# Main.net
KiCad netlist of a schematic drawn in Altium Designer
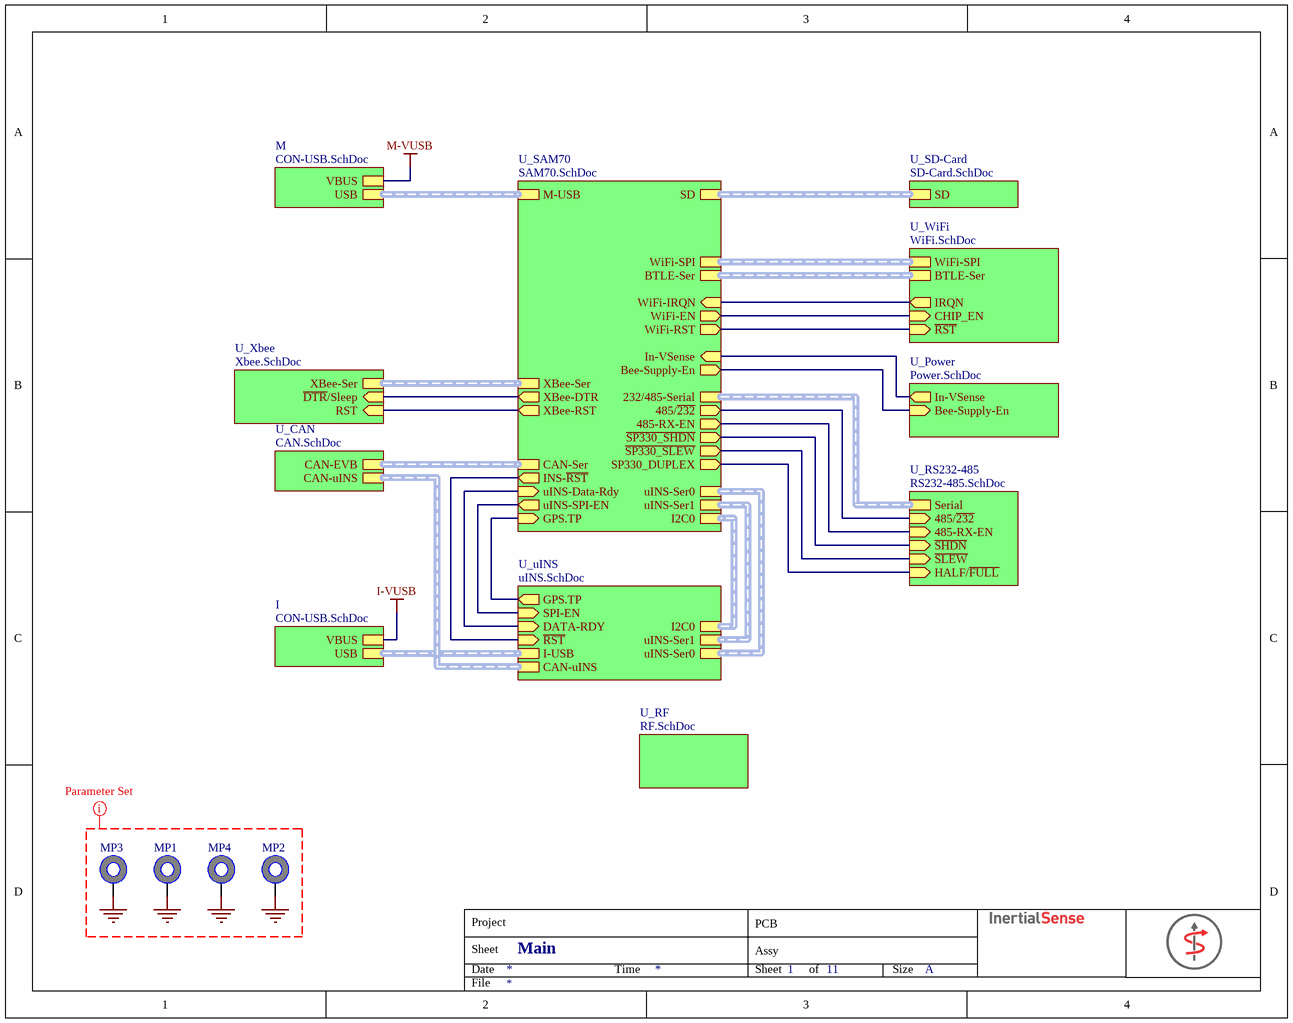
[diagram p0: Main.SchDoc]

(export (version "E")
  (design (tool "Eeschema 10.0.6"))
  (components
    (comp (ref "MP1")
      (value "Standoff")
      (footprint "9774050151R")
      (description "RND STANDOFF M2.5X0.45 STEEL 5MM")
      (fields
        (field (name "MANUFACTURER") "Wurth Electronics")
        (field (name "MANUFACTURER PART NUMBER") "9774050951R")
      )
      (libsource (lib "General") (part "Standoff"))
    )
    (comp (ref "MP2")
      (value "Standoff")
      (footprint "9774050151R")
      (description "RND STANDOFF M2.5X0.45 STEEL 5MM")
      (fields
        (field (name "MANUFACTURER") "Wurth Electronics")
        (field (name "MANUFACTURER PART NUMBER") "9774050951R")
      )
      (libsource (lib "General") (part "Standoff"))
    )
    (comp (ref "MP3")
      (value "Standoff")
      (footprint "9774050151R")
      (description "RND STANDOFF M2.5X0.45 STEEL 5MM")
      (fields
        (field (name "MANUFACTURER") "Wurth Electronics")
        (field (name "MANUFACTURER PART NUMBER") "9774050951R")
      )
      (libsource (lib "General") (part "Standoff"))
    )
    (comp (ref "MP4")
      (value "Standoff")
      (footprint "9774050151R")
      (description "RND STANDOFF M2.5X0.45 STEEL 5MM")
      (fields
        (field (name "MANUFACTURER") "Wurth Electronics")
        (field (name "MANUFACTURER PART NUMBER") "9774050951R")
      )
      (libsource (lib "General") (part "Standoff"))
    )
  )
  (nets
    (net (code "29") (name "GND") (class "Default")
      (node (ref "MP1") (pin "1") (pinfunction "1_1") (pintype "passive"))
      (node (ref "MP2") (pin "1") (pinfunction "1_1") (pintype "passive"))
      (node (ref "MP3") (pin "1") (pinfunction "1_1") (pintype "passive"))
      (node (ref "MP4") (pin "1") (pinfunction "1_1") (pintype "passive"))
    )
  )
)
